# CONTROL.net
KiCad netlist of a schematic drawn in Altium Designer
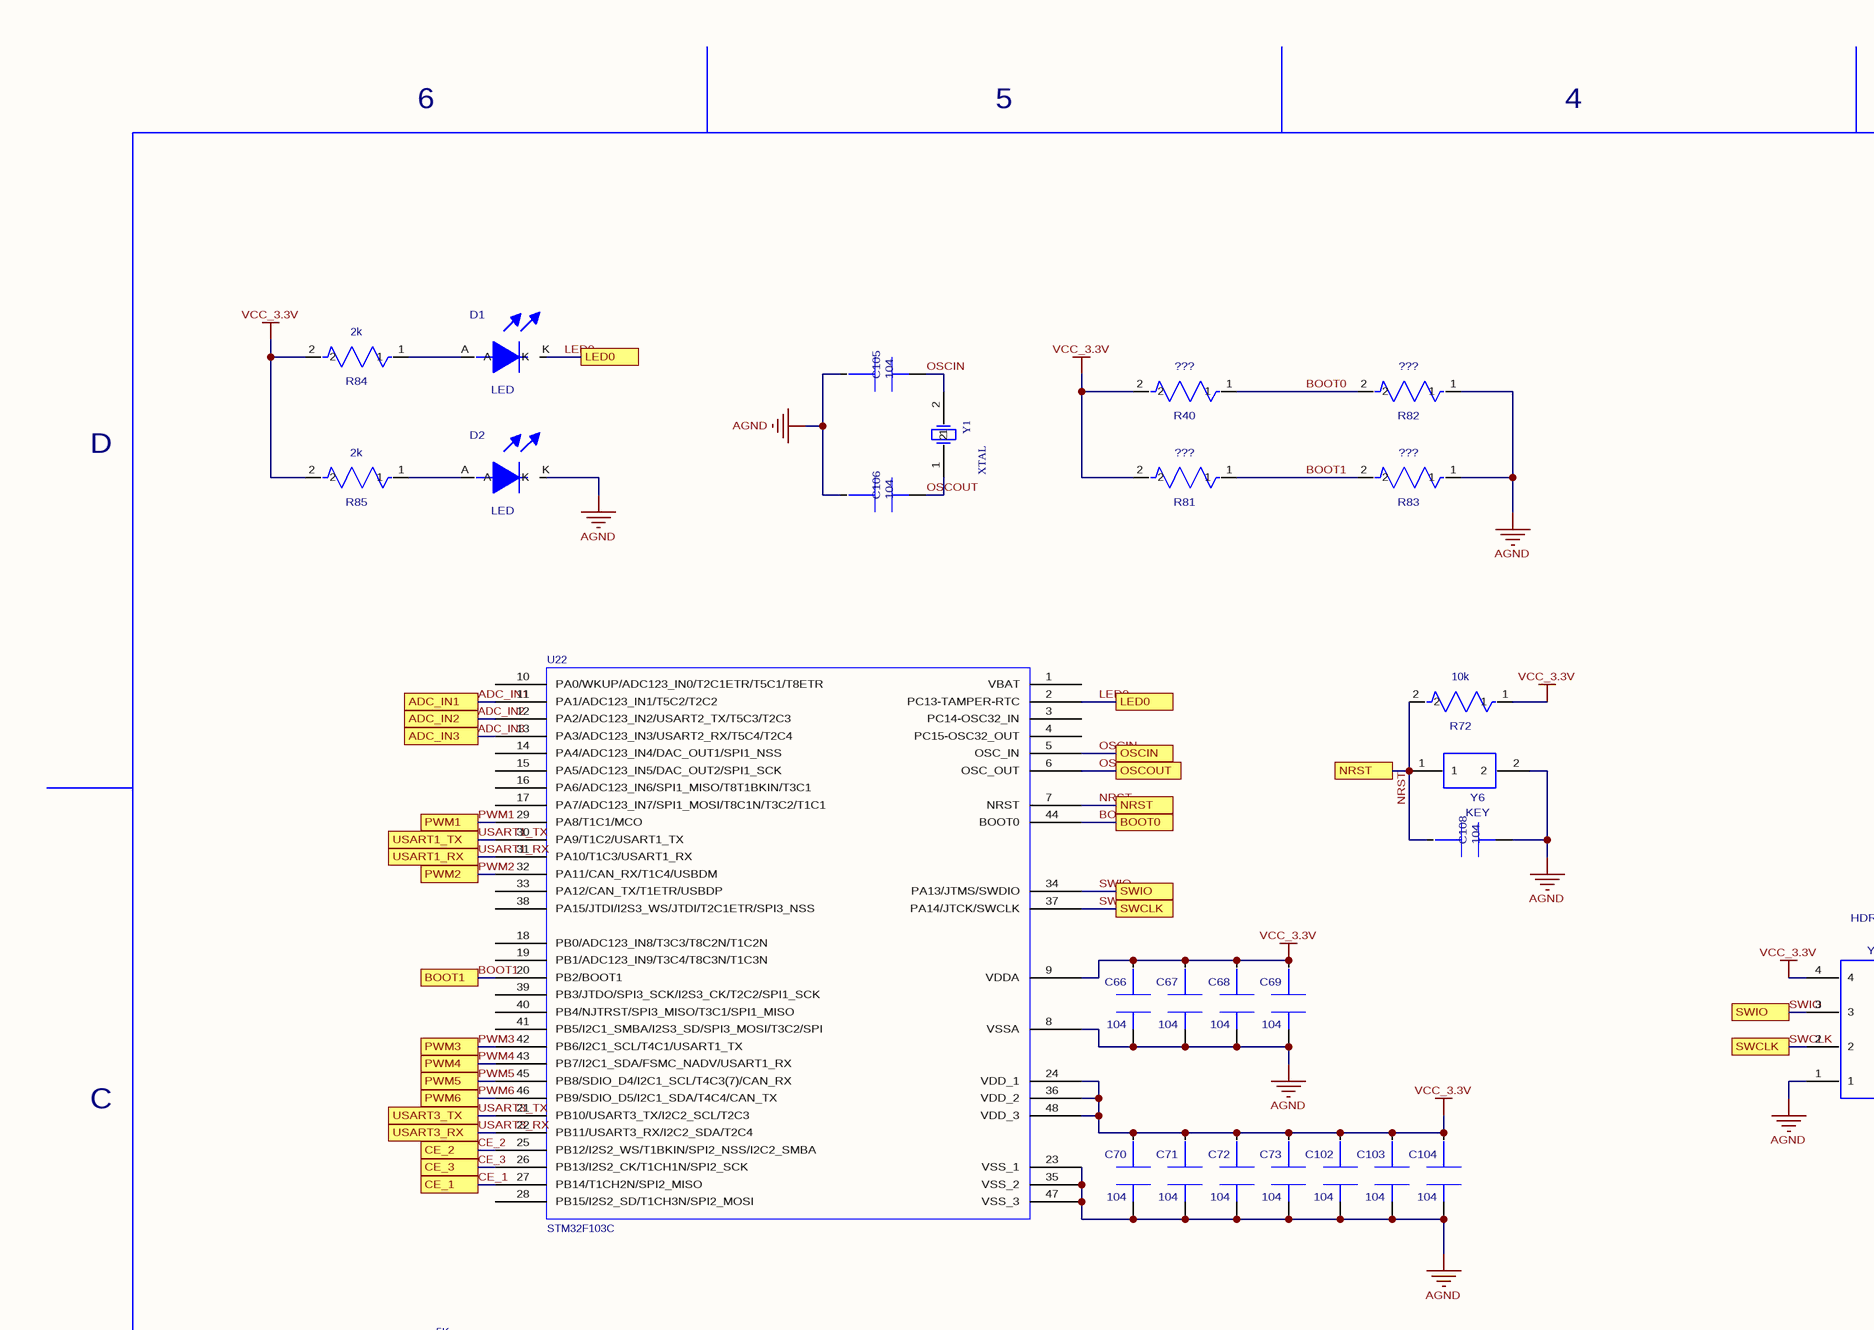
[diagram p0: CONTROL.SchDoc, top left]
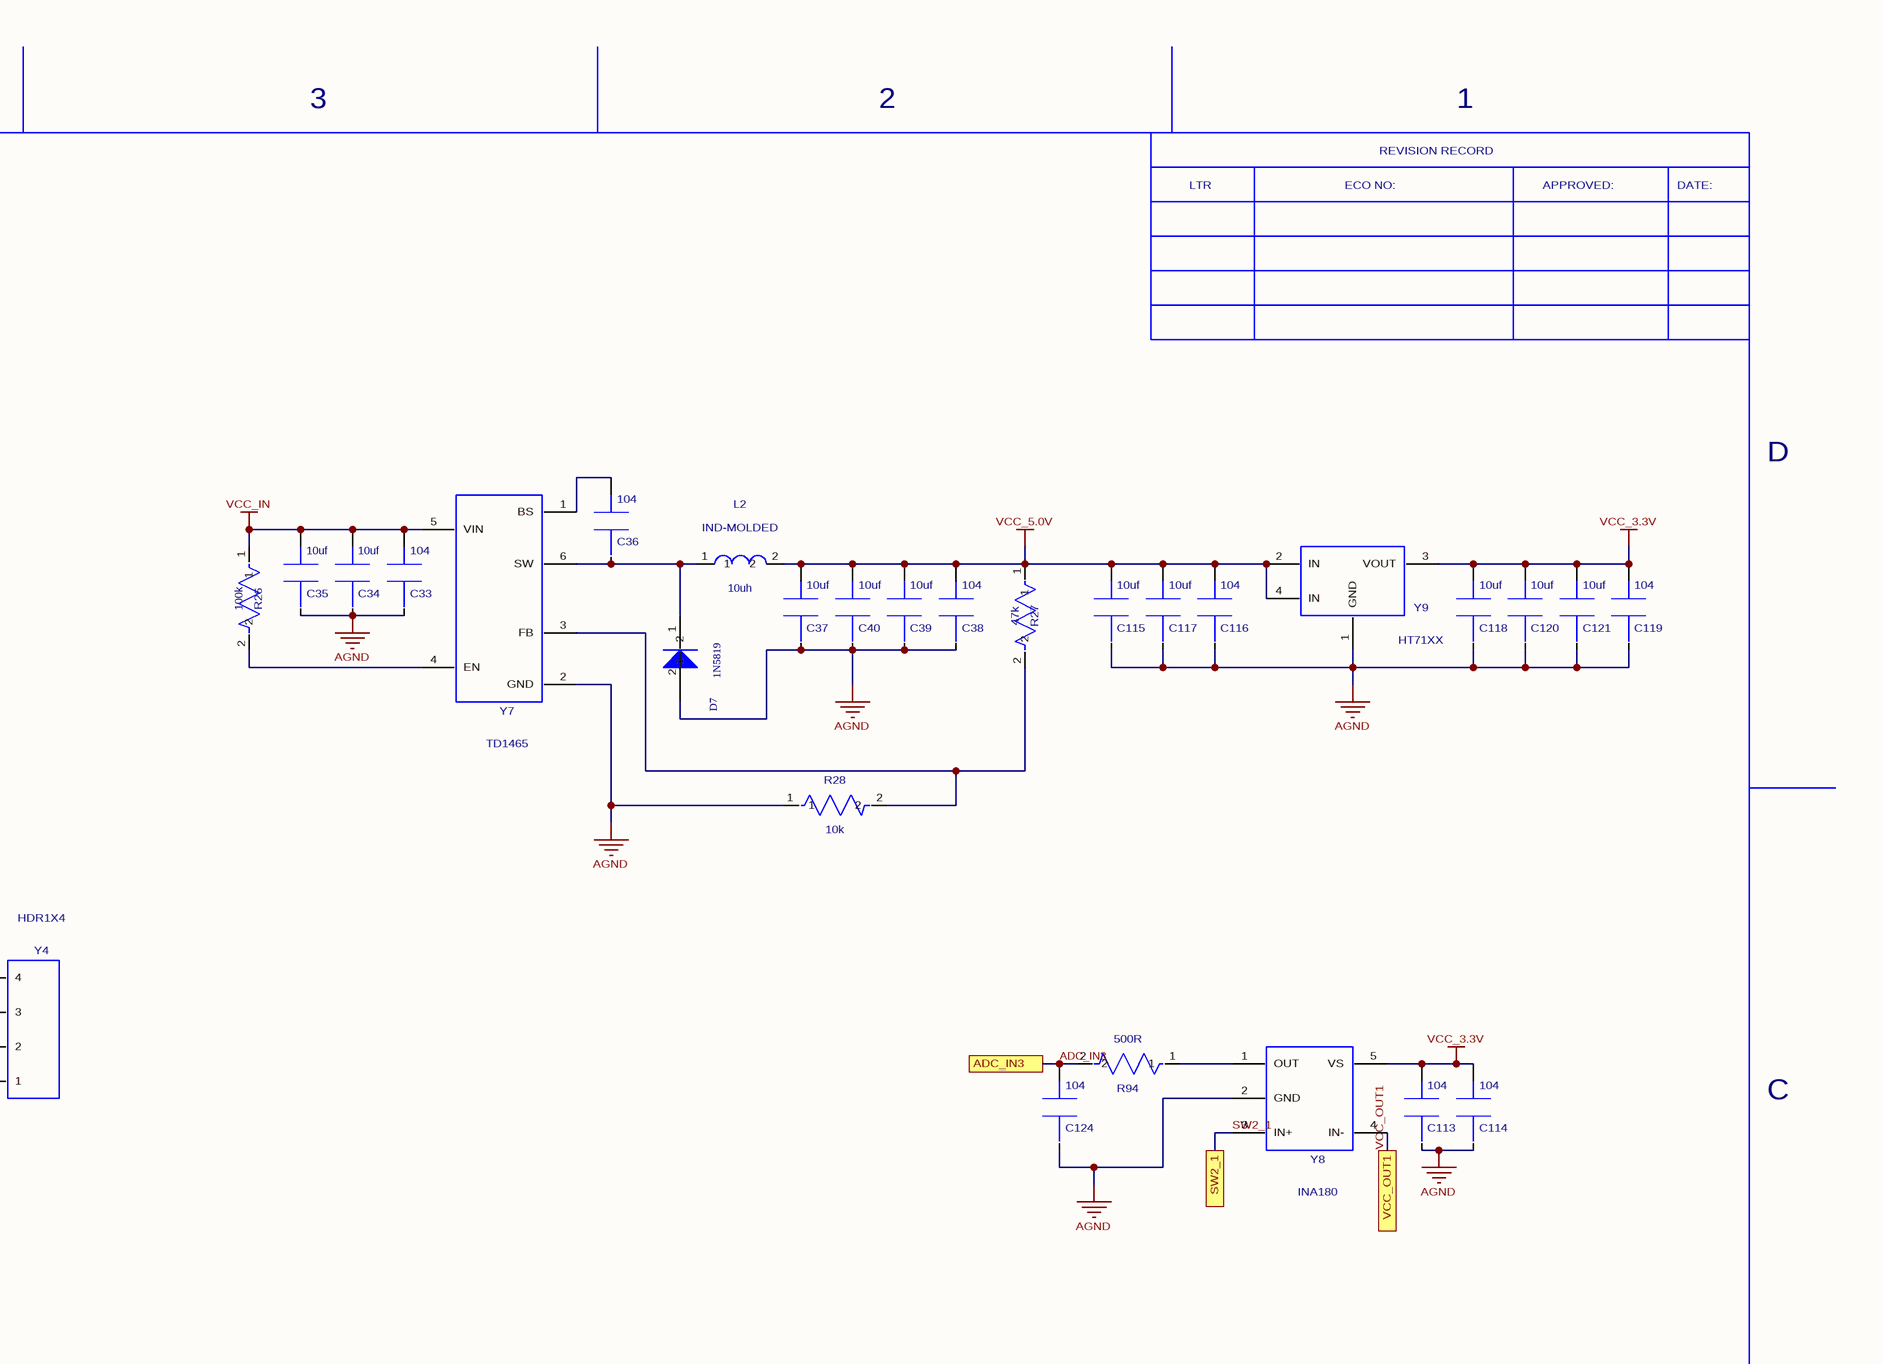
[diagram p1: CONTROL.SchDoc, top right]
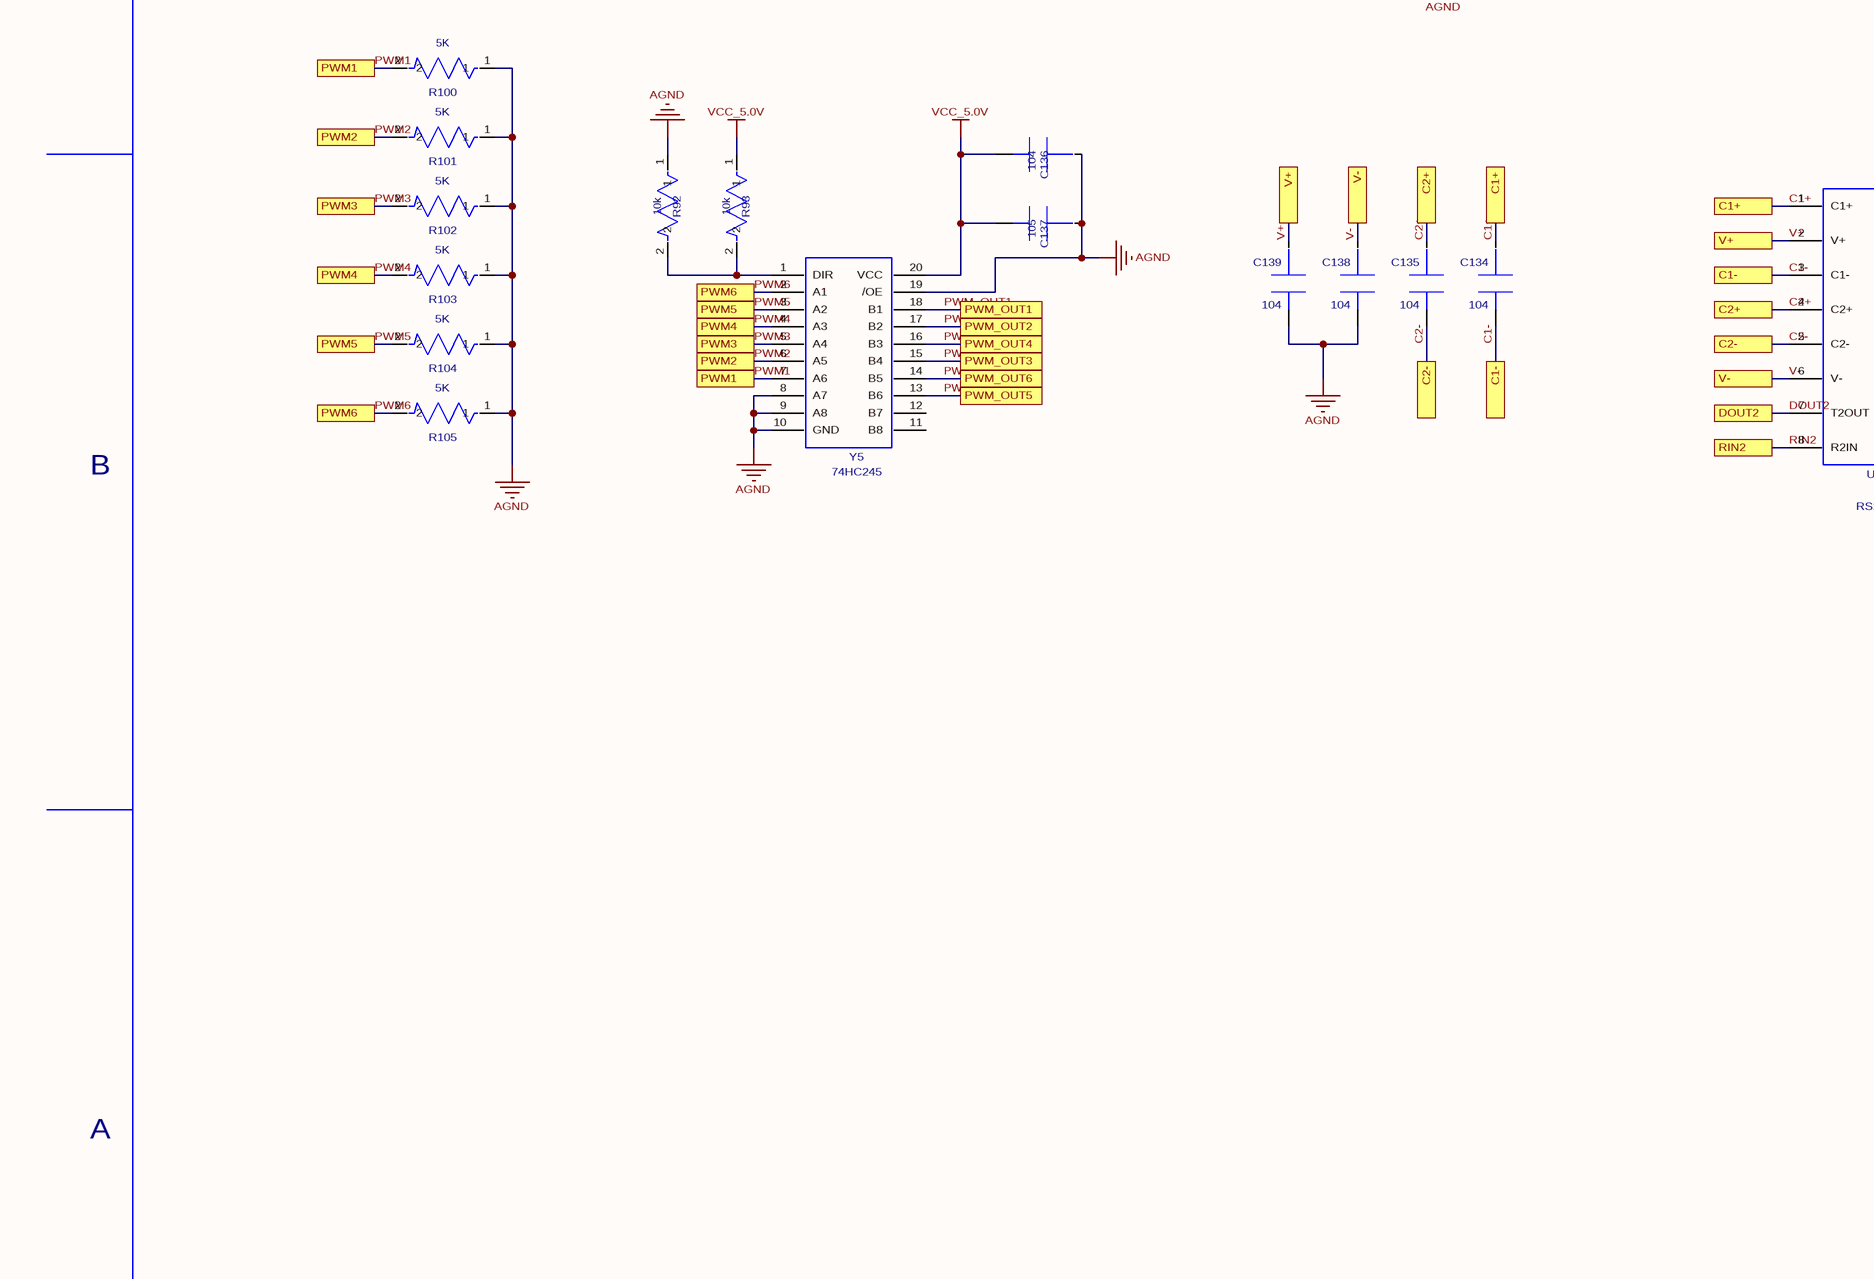
[diagram p2: CONTROL.SchDoc, bottom left]
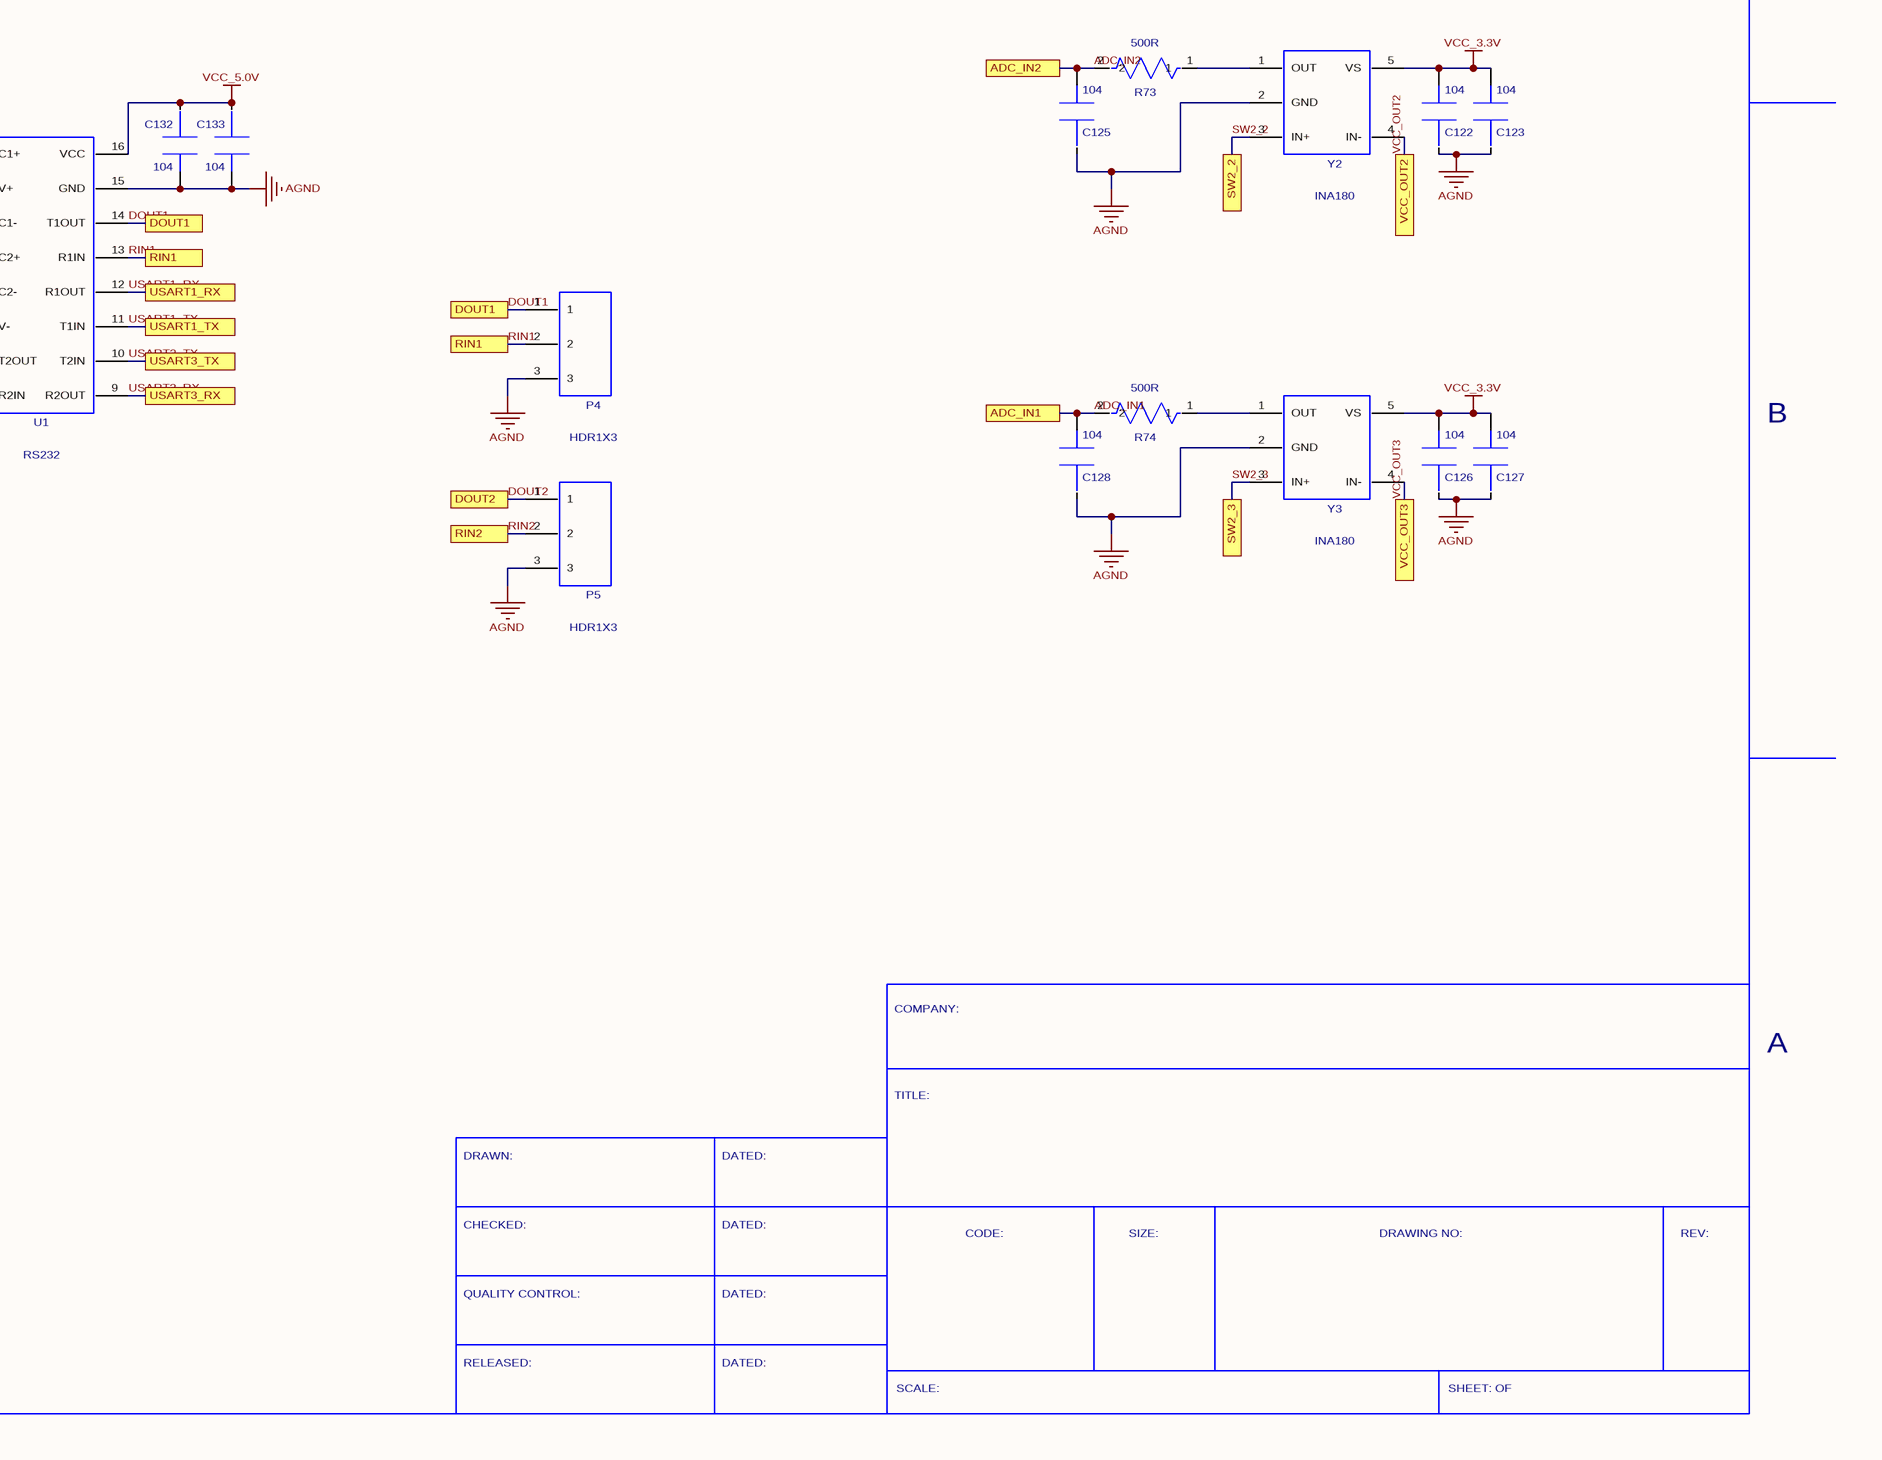
[diagram p3: CONTROL.SchDoc, bottom right]

(export (version "E")
  (design (tool "Eeschema 10.0.6"))
  (components
    (comp (ref "C33")
      (value "104")
      (footprint "0805C")
      (description "RADIAL FILM CAPACITOR, MIL-SPEC SIZE CFR04R SIZE 'C'")
      (fields (field (name "TOLERANCE") "???") (field (name "PART NUMBER") "TBD"))
      (libsource (lib "*") (part "CAP-CFR04R-C"))
    )
    (comp (ref "C34")
      (value "10uf")
      (footprint "0805C")
      (description "RADIAL FILM CAPACITOR, MIL-SPEC SIZE CFR04R SIZE 'C'")
      (fields (field (name "TOLERANCE") "???") (field (name "PART NUMBER") "TBD"))
      (libsource (lib "*") (part "CAP-CFR04R-C"))
    )
    (comp (ref "C35")
      (value "10uf")
      (footprint "0805C")
      (description "RADIAL FILM CAPACITOR, MIL-SPEC SIZE CFR04R SIZE 'C'")
      (fields (field (name "TOLERANCE") "???") (field (name "PART NUMBER") "TBD"))
      (libsource (lib "*") (part "CAP-CFR04R-C"))
    )
    (comp (ref "C36")
      (value "104")
      (footprint "0805C")
      (description "RADIAL FILM CAPACITOR, MIL-SPEC SIZE CFR04R SIZE 'C'")
      (fields (field (name "TOLERANCE") "???") (field (name "PART NUMBER") "TBD"))
      (libsource (lib "*") (part "CAP-CFR04R-C"))
    )
    (comp (ref "C37")
      (value "10uf")
      (footprint "0805C")
      (description "RADIAL FILM CAPACITOR, MIL-SPEC SIZE CFR04R SIZE 'C'")
      (fields (field (name "TOLERANCE") "???") (field (name "PART NUMBER") "TBD"))
      (libsource (lib "*") (part "CAP-CFR04R-C"))
    )
    (comp (ref "C38")
      (value "104")
      (footprint "0805C")
      (description "RADIAL FILM CAPACITOR, MIL-SPEC SIZE CFR04R SIZE 'C'")
      (fields (field (name "TOLERANCE") "???") (field (name "PART NUMBER") "TBD"))
      (libsource (lib "*") (part "CAP-CFR04R-C"))
    )
    (comp (ref "C39")
      (value "10uf")
      (footprint "0805C")
      (description "RADIAL FILM CAPACITOR, MIL-SPEC SIZE CFR04R SIZE 'C'")
      (fields (field (name "TOLERANCE") "???") (field (name "PART NUMBER") "TBD"))
      (libsource (lib "*") (part "CAP-CFR04R-C"))
    )
    (comp (ref "C40")
      (value "10uf")
      (footprint "0805C")
      (description "RADIAL FILM CAPACITOR, MIL-SPEC SIZE CFR04R SIZE 'C'")
      (fields (field (name "TOLERANCE") "???") (field (name "PART NUMBER") "TBD"))
      (libsource (lib "*") (part "CAP-CFR04R-C"))
    )
    (comp (ref "C66")
      (value "104")
      (footprint "0805C")
      (description "RADIAL FILM CAPACITOR, MIL-SPEC SIZE CFR04R SIZE 'C'")
      (fields (field (name "TOLERANCE") "???") (field (name "PART NUMBER") "TBD"))
      (libsource (lib "*") (part "CAP-CFR04R-C"))
    )
    (comp (ref "C67")
      (value "104")
      (footprint "0805C")
      (description "RADIAL FILM CAPACITOR, MIL-SPEC SIZE CFR04R SIZE 'C'")
      (fields (field (name "TOLERANCE") "???") (field (name "PART NUMBER") "TBD"))
      (libsource (lib "*") (part "CAP-CFR04R-C"))
    )
    (comp (ref "C68")
      (value "104")
      (footprint "0805C")
      (description "RADIAL FILM CAPACITOR, MIL-SPEC SIZE CFR04R SIZE 'C'")
      (fields (field (name "TOLERANCE") "???") (field (name "PART NUMBER") "TBD"))
      (libsource (lib "*") (part "CAP-CFR04R-C"))
    )
    (comp (ref "C69")
      (value "104")
      (footprint "0805C")
      (description "RADIAL FILM CAPACITOR, MIL-SPEC SIZE CFR04R SIZE 'C'")
      (fields (field (name "TOLERANCE") "???") (field (name "PART NUMBER") "TBD"))
      (libsource (lib "*") (part "CAP-CFR04R-C"))
    )
    (comp (ref "C70")
      (value "104")
      (footprint "0805C")
      (description "RADIAL FILM CAPACITOR, MIL-SPEC SIZE CFR04R SIZE 'C'")
      (fields (field (name "TOLERANCE") "???") (field (name "PART NUMBER") "TBD"))
      (libsource (lib "*") (part "CAP-CFR04R-C"))
    )
    (comp (ref "C71")
      (value "104")
      (footprint "0805C")
      (description "RADIAL FILM CAPACITOR, MIL-SPEC SIZE CFR04R SIZE 'C'")
      (fields (field (name "TOLERANCE") "???") (field (name "PART NUMBER") "TBD"))
      (libsource (lib "*") (part "CAP-CFR04R-C"))
    )
    (comp (ref "C72")
      (value "104")
      (footprint "0805C")
      (description "RADIAL FILM CAPACITOR, MIL-SPEC SIZE CFR04R SIZE 'C'")
      (fields (field (name "TOLERANCE") "???") (field (name "PART NUMBER") "TBD"))
      (libsource (lib "*") (part "CAP-CFR04R-C"))
    )
    (comp (ref "C73")
      (value "104")
      (footprint "0805C")
      (description "RADIAL FILM CAPACITOR, MIL-SPEC SIZE CFR04R SIZE 'C'")
      (fields (field (name "TOLERANCE") "???") (field (name "PART NUMBER") "TBD"))
      (libsource (lib "*") (part "CAP-CFR04R-C"))
    )
    (comp (ref "C102")
      (value "104")
      (footprint "0805C")
      (description "RADIAL FILM CAPACITOR, MIL-SPEC SIZE CFR04R SIZE 'C'")
      (fields (field (name "TOLERANCE") "???") (field (name "PART NUMBER") "TBD"))
      (libsource (lib "*") (part "CAP-CFR04R-C"))
    )
    (comp (ref "C103")
      (value "104")
      (footprint "0805C")
      (description "RADIAL FILM CAPACITOR, MIL-SPEC SIZE CFR04R SIZE 'C'")
      (fields (field (name "TOLERANCE") "???") (field (name "PART NUMBER") "TBD"))
      (libsource (lib "*") (part "CAP-CFR04R-C"))
    )
    (comp (ref "C104")
      (value "104")
      (footprint "0805C")
      (description "RADIAL FILM CAPACITOR, MIL-SPEC SIZE CFR04R SIZE 'C'")
      (fields (field (name "TOLERANCE") "???") (field (name "PART NUMBER") "TBD"))
      (libsource (lib "*") (part "CAP-CFR04R-C"))
    )
    (comp (ref "C105")
      (value "104")
      (footprint "0805C")
      (description "RADIAL FILM CAPACITOR, MIL-SPEC SIZE CFR04R SIZE 'C'")
      (fields (field (name "TOLERANCE") "???") (field (name "PART NUMBER") "TBD"))
      (libsource (lib "*") (part "CAP-CFR04R-C"))
    )
    (comp (ref "C106")
      (value "104")
      (footprint "0805C")
      (description "RADIAL FILM CAPACITOR, MIL-SPEC SIZE CFR04R SIZE 'C'")
      (fields (field (name "TOLERANCE") "???") (field (name "PART NUMBER") "TBD"))
      (libsource (lib "*") (part "CAP-CFR04R-C"))
    )
    (comp (ref "C108")
      (value "104")
      (footprint "0805C")
      (description "RADIAL FILM CAPACITOR, MIL-SPEC SIZE CFR04R SIZE 'C'")
      (fields (field (name "TOLERANCE") "???") (field (name "PART NUMBER") "TBD"))
      (libsource (lib "*") (part "CAP-CFR04R-C"))
    )
    (comp (ref "C113")
      (value "104")
      (footprint "0805C")
      (description "RADIAL FILM CAPACITOR, MIL-SPEC SIZE CFR04R SIZE 'C'")
      (fields (field (name "TOLERANCE") "???") (field (name "PART NUMBER") "TBD"))
      (libsource (lib "*") (part "CAP-CFR04R-C"))
    )
    (comp (ref "C114")
      (value "104")
      (footprint "0805C")
      (description "RADIAL FILM CAPACITOR, MIL-SPEC SIZE CFR04R SIZE 'C'")
      (fields (field (name "TOLERANCE") "???") (field (name "PART NUMBER") "TBD"))
      (libsource (lib "*") (part "CAP-CFR04R-C"))
    )
    (comp (ref "C115")
      (value "10uf")
      (footprint "0805C")
      (description "RADIAL FILM CAPACITOR, MIL-SPEC SIZE CFR04R SIZE 'C'")
      (fields (field (name "TOLERANCE") "???") (field (name "PART NUMBER") "TBD"))
      (libsource (lib "*") (part "CAP-CFR04R-C"))
    )
    (comp (ref "C116")
      (value "104")
      (footprint "0805C")
      (description "RADIAL FILM CAPACITOR, MIL-SPEC SIZE CFR04R SIZE 'C'")
      (fields (field (name "TOLERANCE") "???") (field (name "PART NUMBER") "TBD"))
      (libsource (lib "*") (part "CAP-CFR04R-C"))
    )
    (comp (ref "C117")
      (value "10uf")
      (footprint "0805C")
      (description "RADIAL FILM CAPACITOR, MIL-SPEC SIZE CFR04R SIZE 'C'")
      (fields (field (name "TOLERANCE") "???") (field (name "PART NUMBER") "TBD"))
      (libsource (lib "*") (part "CAP-CFR04R-C"))
    )
    (comp (ref "C118")
      (value "10uf")
      (footprint "0805C")
      (description "RADIAL FILM CAPACITOR, MIL-SPEC SIZE CFR04R SIZE 'C'")
      (fields (field (name "TOLERANCE") "???") (field (name "PART NUMBER") "TBD"))
      (libsource (lib "*") (part "CAP-CFR04R-C"))
    )
    (comp (ref "C119")
      (value "104")
      (footprint "0805C")
      (description "RADIAL FILM CAPACITOR, MIL-SPEC SIZE CFR04R SIZE 'C'")
      (fields (field (name "TOLERANCE") "???") (field (name "PART NUMBER") "TBD"))
      (libsource (lib "*") (part "CAP-CFR04R-C"))
    )
    (comp (ref "C120")
      (value "10uf")
      (footprint "0805C")
      (description "RADIAL FILM CAPACITOR, MIL-SPEC SIZE CFR04R SIZE 'C'")
      (fields (field (name "TOLERANCE") "???") (field (name "PART NUMBER") "TBD"))
      (libsource (lib "*") (part "CAP-CFR04R-C"))
    )
    (comp (ref "C121")
      (value "10uf")
      (footprint "0805C")
      (description "RADIAL FILM CAPACITOR, MIL-SPEC SIZE CFR04R SIZE 'C'")
      (fields (field (name "TOLERANCE") "???") (field (name "PART NUMBER") "TBD"))
      (libsource (lib "*") (part "CAP-CFR04R-C"))
    )
    (comp (ref "C122")
      (value "104")
      (footprint "0805C")
      (description "RADIAL FILM CAPACITOR, MIL-SPEC SIZE CFR04R SIZE 'C'")
      (fields (field (name "TOLERANCE") "???") (field (name "PART NUMBER") "TBD"))
      (libsource (lib "*") (part "CAP-CFR04R-C"))
    )
    (comp (ref "C123")
      (value "104")
      (footprint "0805C")
      (description "RADIAL FILM CAPACITOR, MIL-SPEC SIZE CFR04R SIZE 'C'")
      (fields (field (name "TOLERANCE") "???") (field (name "PART NUMBER") "TBD"))
      (libsource (lib "*") (part "CAP-CFR04R-C"))
    )
    (comp (ref "C124")
      (value "104")
      (footprint "0805C")
      (description "RADIAL FILM CAPACITOR, MIL-SPEC SIZE CFR04R SIZE 'C'")
      (fields (field (name "TOLERANCE") "???") (field (name "PART NUMBER") "TBD"))
      (libsource (lib "*") (part "CAP-CFR04R-C"))
    )
    (comp (ref "C125")
      (value "104")
      (footprint "0805C")
      (description "RADIAL FILM CAPACITOR, MIL-SPEC SIZE CFR04R SIZE 'C'")
      (fields (field (name "TOLERANCE") "???") (field (name "PART NUMBER") "TBD"))
      (libsource (lib "*") (part "CAP-CFR04R-C"))
    )
    (comp (ref "C126")
      (value "104")
      (footprint "0805C")
      (description "RADIAL FILM CAPACITOR, MIL-SPEC SIZE CFR04R SIZE 'C'")
      (fields (field (name "TOLERANCE") "???") (field (name "PART NUMBER") "TBD"))
      (libsource (lib "*") (part "CAP-CFR04R-C"))
    )
    (comp (ref "C127")
      (value "104")
      (footprint "0805C")
      (description "RADIAL FILM CAPACITOR, MIL-SPEC SIZE CFR04R SIZE 'C'")
      (fields (field (name "TOLERANCE") "???") (field (name "PART NUMBER") "TBD"))
      (libsource (lib "*") (part "CAP-CFR04R-C"))
    )
    (comp (ref "C128")
      (value "104")
      (footprint "0805C")
      (description "RADIAL FILM CAPACITOR, MIL-SPEC SIZE CFR04R SIZE 'C'")
      (fields (field (name "TOLERANCE") "???") (field (name "PART NUMBER") "TBD"))
      (libsource (lib "*") (part "CAP-CFR04R-C"))
    )
    (comp (ref "C132")
      (value "104")
      (footprint "0805C")
      (description "RADIAL FILM CAPACITOR, MIL-SPEC SIZE CFR04R SIZE 'C'")
      (fields (field (name "TOLERANCE") "???") (field (name "PART NUMBER") "TBD"))
      (libsource (lib "*") (part "CAP-CFR04R-C"))
    )
    (comp (ref "C133")
      (value "104")
      (footprint "0805C")
      (description "RADIAL FILM CAPACITOR, MIL-SPEC SIZE CFR04R SIZE 'C'")
      (fields (field (name "TOLERANCE") "???") (field (name "PART NUMBER") "TBD"))
      (libsource (lib "*") (part "CAP-CFR04R-C"))
    )
    (comp (ref "C134")
      (value "104")
      (footprint "0805C")
      (description "RADIAL FILM CAPACITOR, MIL-SPEC SIZE CFR04R SIZE 'C'")
      (fields (field (name "TOLERANCE") "???") (field (name "PART NUMBER") "TBD"))
      (libsource (lib "*") (part "CAP-CFR04R-C"))
    )
    (comp (ref "C135")
      (value "104")
      (footprint "0805C")
      (description "RADIAL FILM CAPACITOR, MIL-SPEC SIZE CFR04R SIZE 'C'")
      (fields (field (name "TOLERANCE") "???") (field (name "PART NUMBER") "TBD"))
      (libsource (lib "*") (part "CAP-CFR04R-C"))
    )
    (comp (ref "C136")
      (value "104")
      (footprint "0805C")
      (description "RADIAL FILM CAPACITOR, MIL-SPEC SIZE CFR04R SIZE 'C'")
      (fields (field (name "TOLERANCE") "???") (field (name "PART NUMBER") "TBD"))
      (libsource (lib "*") (part "CAP-CFR04R-C"))
    )
    (comp (ref "C137")
      (value "105")
      (footprint "0603C")
      (description "RADIAL FILM CAPACITOR, MIL-SPEC SIZE CFR04R SIZE 'C'")
      (fields (field (name "TOLERANCE") "???") (field (name "PART NUMBER") "TBD"))
      (libsource (lib "*") (part "CAP-CFR04R-C"))
    )
    (comp (ref "C138")
      (value "104")
      (footprint "0805C")
      (description "RADIAL FILM CAPACITOR, MIL-SPEC SIZE CFR04R SIZE 'C'")
      (fields (field (name "TOLERANCE") "???") (field (name "PART NUMBER") "TBD"))
      (libsource (lib "*") (part "CAP-CFR04R-C"))
    )
    (comp (ref "C139")
      (value "104")
      (footprint "0805C")
      (description "RADIAL FILM CAPACITOR, MIL-SPEC SIZE CFR04R SIZE 'C'")
      (fields (field (name "TOLERANCE") "???") (field (name "PART NUMBER") "TBD"))
      (libsource (lib "*") (part "CAP-CFR04R-C"))
    )
    (comp (ref "D1")
      (value "LED")
      (footprint "0805D")
      (description "LIGHT EMITTING DIODE")
      (libsource (lib "*") (part "LED"))
    )
    (comp (ref "D2")
      (value "LED")
      (footprint "0805D")
      (description "LIGHT EMITTING DIODE")
      (libsource (lib "*") (part "LED"))
    )
    (comp (ref "D7")
      (value "1N5819")
      (footprint "SOD-123_L2.8-W1.8-LS3.7-RD")
      (description "High Conductance Fast Diode")
      (fields (field (name "PUBLISHER") "Altium Limited"))
      (libsource (lib "*") (part "DIODE_1N4148"))
    )
    (comp (ref "L2")
      (value "IND-MOLDED")
      (footprint "L-SMD-0630")
      (description "MOLDED INDUCTOR, 0.5\" PIN SPACING")
      (fields (field (name "ALTIUM_VALUE") "10uh"))
      (libsource (lib "*") (part "IND-MOLDED"))
    )
    (comp (ref "P4") (value "HDR1X3") (footprint "POST_3") (libsource (lib "*") (part "HDR1X3")))
    (comp (ref "P5") (value "HDR1X3") (footprint "POST_3") (libsource (lib "*") (part "HDR1X3")))
    (comp (ref "R26")
      (value "100k")
      (footprint "0603R")
      (description "WIRE WOUND RESISTOR 3.4 X 7.05 MM")
      (fields (field (name "Comment") "RES-WR1"))
      (libsource (lib "*") (part "RES-WR1"))
    )
    (comp (ref "R27")
      (value "47k")
      (footprint "0603R")
      (description "WIRE WOUND RESISTOR 3.4 X 7.05 MM")
      (fields (field (name "Comment") "RES-WR1"))
      (libsource (lib "*") (part "RES-WR1"))
    )
    (comp (ref "R28")
      (value "10k")
      (footprint "0603R")
      (description "WIRE WOUND RESISTOR 3.4 X 7.05 MM")
      (fields (field (name "Comment") "RES-WR1"))
      (libsource (lib "*") (part "RES-WR1"))
    )
    (comp (ref "R40")
      (value "???")
      (footprint "0603R")
      (description "WIRE WOUND RESISTOR 3.4 X 7.05 MM")
      (fields (field (name "Comment") "RES-WR1"))
      (libsource (lib "*") (part "RES-WR1"))
    )
    (comp (ref "R72")
      (value "10k")
      (footprint "0603R")
      (description "WIRE WOUND RESISTOR 3.4 X 7.05 MM")
      (fields (field (name "Comment") "RES-WR1"))
      (libsource (lib "*") (part "RES-WR1"))
    )
    (comp (ref "R73")
      (value "500R")
      (footprint "0603R")
      (description "WIRE WOUND RESISTOR 3.4 X 7.05 MM")
      (fields (field (name "Comment") "RES-WR1"))
      (libsource (lib "*") (part "RES-WR1"))
    )
    (comp (ref "R74")
      (value "500R")
      (footprint "0603R")
      (description "WIRE WOUND RESISTOR 3.4 X 7.05 MM")
      (fields (field (name "Comment") "RES-WR1"))
      (libsource (lib "*") (part "RES-WR1"))
    )
    (comp (ref "R81")
      (value "???")
      (footprint "0603R")
      (description "WIRE WOUND RESISTOR 3.4 X 7.05 MM")
      (fields (field (name "Comment") "RES-WR1"))
      (libsource (lib "*") (part "RES-WR1"))
    )
    (comp (ref "R82")
      (value "???")
      (footprint "0603R")
      (description "WIRE WOUND RESISTOR 3.4 X 7.05 MM")
      (fields (field (name "Comment") "RES-WR1"))
      (libsource (lib "*") (part "RES-WR1"))
    )
    (comp (ref "R83")
      (value "???")
      (footprint "0603R")
      (description "WIRE WOUND RESISTOR 3.4 X 7.05 MM")
      (fields (field (name "Comment") "RES-WR1"))
      (libsource (lib "*") (part "RES-WR1"))
    )
    (comp (ref "R84")
      (value "2k")
      (footprint "0805R")
      (description "WIRE WOUND RESISTOR 3.4 X 7.05 MM")
      (fields (field (name "Comment") "RES-WR1"))
      (libsource (lib "*") (part "RES-WR1"))
    )
    (comp (ref "R85")
      (value "2k")
      (footprint "0805R")
      (description "WIRE WOUND RESISTOR 3.4 X 7.05 MM")
      (fields (field (name "Comment") "RES-WR1"))
      (libsource (lib "*") (part "RES-WR1"))
    )
    (comp (ref "R92")
      (value "10k")
      (footprint "0603R")
      (description "WIRE WOUND RESISTOR 3.4 X 7.05 MM")
      (fields (field (name "Comment") "RES-WR1"))
      (libsource (lib "*") (part "RES-WR1"))
    )
    (comp (ref "R93")
      (value "10k")
      (footprint "0603R")
      (description "WIRE WOUND RESISTOR 3.4 X 7.05 MM")
      (fields (field (name "Comment") "RES-WR1"))
      (libsource (lib "*") (part "RES-WR1"))
    )
    (comp (ref "R94")
      (value "500R")
      (footprint "0603R")
      (description "WIRE WOUND RESISTOR 3.4 X 7.05 MM")
      (fields (field (name "Comment") "RES-WR1"))
      (libsource (lib "*") (part "RES-WR1"))
    )
    (comp (ref "R100")
      (value "5K")
      (footprint "0603R")
      (description "WIRE WOUND RESISTOR 3.4 X 7.05 MM")
      (fields (field (name "Comment") "RES-WR1"))
      (libsource (lib "*") (part "RES-WR1"))
    )
    (comp (ref "R101")
      (value "5K")
      (footprint "0603R")
      (description "WIRE WOUND RESISTOR 3.4 X 7.05 MM")
      (fields (field (name "Comment") "RES-WR1"))
      (libsource (lib "*") (part "RES-WR1"))
    )
    (comp (ref "R102")
      (value "5K")
      (footprint "0603R")
      (description "WIRE WOUND RESISTOR 3.4 X 7.05 MM")
      (fields (field (name "Comment") "RES-WR1"))
      (libsource (lib "*") (part "RES-WR1"))
    )
    (comp (ref "R103")
      (value "5K")
      (footprint "0603R")
      (description "WIRE WOUND RESISTOR 3.4 X 7.05 MM")
      (fields (field (name "Comment") "RES-WR1"))
      (libsource (lib "*") (part "RES-WR1"))
    )
    (comp (ref "R104")
      (value "5K")
      (footprint "0603R")
      (description "WIRE WOUND RESISTOR 3.4 X 7.05 MM")
      (fields (field (name "Comment") "RES-WR1"))
      (libsource (lib "*") (part "RES-WR1"))
    )
    (comp (ref "R105")
      (value "5K")
      (footprint "0603R")
      (description "WIRE WOUND RESISTOR 3.4 X 7.05 MM")
      (fields (field (name "Comment") "RES-WR1"))
      (libsource (lib "*") (part "RES-WR1"))
    )
    (comp (ref "U1")
      (value "RS232")
      (footprint "SOP-16_L9.9-W3.9-P1.27-LS6.1-BL")
      (libsource (lib "*") (part "RS232"))
    )
    (comp (ref "U22")
      (value "STM32F103C")
      (footprint "LQFP-48_M")
      (description "STM32单片机48引脚")
      (libsource (lib "*") (part "STM32F103C"))
    )
    (comp (ref "Y1")
      (value "XTAL")
      (footprint "HC-49S_L11.4-W4.8")
      (description "Crystal Oscillator")
      (fields (field (name "PUBLISHER") "Altium Limited"))
      (libsource (lib "*") (part "XTAL"))
    )
    (comp (ref "Y2")
      (value "INA180")
      (footprint "SOT-23-5_L3.0-W1.7-P0.95-LS2.8-BL")
      (libsource (lib "*") (part "INA180"))
    )
    (comp (ref "Y3")
      (value "INA180")
      (footprint "SOT-23-5_L3.0-W1.7-P0.95-LS2.8-BL")
      (libsource (lib "*") (part "INA180"))
    )
    (comp (ref "Y4") (value "HDR1X4") (footprint "HDR1X4") (libsource (lib "*") (part "HDR1X4")))
    (comp (ref "Y5")
      (value "74HC245")
      (footprint "TSSOP-20_L6.5-W4.4-P0.65-LS6.4-BL")
      (libsource (lib "*") (part "74HC04"))
    )
    (comp (ref "Y6") (value "KEY") (footprint "KEY_3_6_2.5") (libsource (lib "*") (part "KEY")))
    (comp (ref "Y7") (value "TD1465") (footprint "SOT-23-6") (libsource (lib "*") (part "TD1465")))
    (comp (ref "Y8")
      (value "INA180")
      (footprint "SOT-23-5_L3.0-W1.7-P0.95-LS2.8-BL")
      (libsource (lib "*") (part "INA180"))
    )
    (comp (ref "Y9")
      (value "HT71XX")
      (footprint "SOT-89-3_L4.5-W2.5-P1.50-LS4.2-BR")
      (libsource (lib "*") (part "HT71XX"))
    )
  )
  (nets
    (net (code "1") (name "/ADC_IN1") (class "Default")
      (node (ref "C128") (pin "2") (pinfunction "2_2") (pintype "passive"))
      (node (ref "R74") (pin "2") (pinfunction "2_2") (pintype "passive"))
      (node (ref "U22") (pin "11") (pinfunction "PA1/ADC123_IN1/T5C2/T2C2_11") (pintype "passive"))
    )
    (net (code "2") (name "/ADC_IN2") (class "Default")
      (node (ref "C125") (pin "2") (pinfunction "2_2") (pintype "passive"))
      (node (ref "R73") (pin "2") (pinfunction "2_2") (pintype "passive"))
      (node (ref "U22") (pin "12") (pinfunction "PA2/ADC123_IN2/USART2_TX/T5C3/T2C3_12") (pintype "passive"))
    )
    (net (code "3") (name "/ADC_IN3") (class "Default")
      (node (ref "C124") (pin "2") (pinfunction "2_2") (pintype "passive"))
      (node (ref "R94") (pin "2") (pinfunction "2_2") (pintype "passive"))
      (node (ref "U22") (pin "13") (pinfunction "PA3/ADC123_IN3/USART2_RX/T5C4/T2C4_13") (pintype "passive"))
    )
    (net (code "4") (name "/BOOT0") (class "Default")
      (node (ref "R40") (pin "1") (pinfunction "1_1") (pintype "passive"))
      (node (ref "R82") (pin "2") (pinfunction "2_2") (pintype "passive"))
      (node (ref "U22") (pin "44") (pinfunction "BOOT0_44") (pintype "passive"))
    )
    (net (code "5") (name "/BOOT1") (class "Default")
      (node (ref "R81") (pin "1") (pinfunction "1_1") (pintype "passive"))
      (node (ref "R83") (pin "2") (pinfunction "2_2") (pintype "passive"))
      (node (ref "U22") (pin "20") (pinfunction "PB2/BOOT1_20") (pintype "passive"))
    )
    (net (code "6") (name "/C1+") (class "Default")
      (node (ref "C134") (pin "1") (pinfunction "1_1") (pintype "passive"))
      (node (ref "U1") (pin "1") (pinfunction "C1+_1") (pintype "passive"))
    )
    (net (code "7") (name "/C1-") (class "Default")
      (node (ref "C134") (pin "2") (pinfunction "2_2") (pintype "passive"))
      (node (ref "U1") (pin "3") (pinfunction "C1-_3") (pintype "passive"))
    )
    (net (code "8") (name "/C2+") (class "Default")
      (node (ref "C135") (pin "1") (pinfunction "1_1") (pintype "passive"))
      (node (ref "U1") (pin "4") (pinfunction "C2+_4") (pintype "passive"))
    )
    (net (code "9") (name "/C2-") (class "Default")
      (node (ref "C135") (pin "2") (pinfunction "2_2") (pintype "passive"))
      (node (ref "U1") (pin "5") (pinfunction "C2-_5") (pintype "passive"))
    )
    (net (code "10") (name "/CE_1") (class "Default")
      (node (ref "U22") (pin "27") (pinfunction "PB14/T1CH2N/SPI2_MISO_27") (pintype "passive"))
    )
    (net (code "11") (name "/CE_2") (class "Default")
      (node (ref "U22") (pin "25") (pinfunction "PB12/I2S2_WS/T1BKIN/SPI2_NSS/I2C2_SMBA_25") (pintype "passive"))
    )
    (net (code "12") (name "/CE_3") (class "Default")
      (node (ref "U22") (pin "26") (pinfunction "PB13/I2S2_CK/T1CH1N/SPI2_SCK_26") (pintype "passive"))
    )
    (net (code "13") (name "/DOUT1") (class "Default")
      (node (ref "P4") (pin "1") (pinfunction "1_1") (pintype "passive"))
      (node (ref "U1") (pin "14") (pinfunction "T1OUT_14") (pintype "passive"))
    )
    (net (code "14") (name "/DOUT2") (class "Default")
      (node (ref "P5") (pin "1") (pinfunction "1_1") (pintype "passive"))
      (node (ref "U1") (pin "7") (pinfunction "T2OUT_7") (pintype "passive"))
    )
    (net (code "15") (name "/LED0") (class "Default")
      (node (ref "D1") (pin "K") (pinfunction "K_K") (pintype "passive"))
      (node (ref "U22") (pin "2") (pinfunction "PC13-TAMPER-RTC_2") (pintype "passive"))
    )
    (net (code "16") (name "/NRST") (class "Default")
      (node (ref "C108") (pin "1") (pinfunction "1_1") (pintype "passive"))
      (node (ref "R72") (pin "2") (pinfunction "2_2") (pintype "passive"))
      (node (ref "U22") (pin "7") (pinfunction "NRST_7") (pintype "passive"))
      (node (ref "Y6") (pin "1") (pinfunction "1_1") (pintype "passive"))
    )
    (net (code "17") (name "/OSCIN") (class "Default")
      (node (ref "C105") (pin "2") (pinfunction "2_2") (pintype "passive"))
      (node (ref "U22") (pin "5") (pinfunction "OSC_IN_5") (pintype "passive"))
      (node (ref "Y1") (pin "2") (pinfunction "2_2") (pintype "passive"))
    )
    (net (code "18") (name "/OSCOUT") (class "Default")
      (node (ref "C106") (pin "2") (pinfunction "2_2") (pintype "passive"))
      (node (ref "U22") (pin "6") (pinfunction "OSC_OUT_6") (pintype "passive"))
      (node (ref "Y1") (pin "1") (pinfunction "1_1") (pintype "passive"))
    )
    (net (code "19") (name "/PWM1") (class "Default")
      (node (ref "R100") (pin "2") (pinfunction "2_2") (pintype "passive"))
      (node (ref "U22") (pin "29") (pinfunction "PA8/T1C1/MCO_29") (pintype "passive"))
      (node (ref "Y5") (pin "7") (pinfunction "A6_7") (pintype "passive"))
    )
    (net (code "20") (name "/PWM2") (class "Default")
      (node (ref "R101") (pin "2") (pinfunction "2_2") (pintype "passive"))
      (node (ref "U22") (pin "32") (pinfunction "PA11/CAN_RX/T1C4/USBDM_32") (pintype "passive"))
      (node (ref "Y5") (pin "6") (pinfunction "A5_6") (pintype "passive"))
    )
    (net (code "21") (name "/PWM3") (class "Default")
      (node (ref "R102") (pin "2") (pinfunction "2_2") (pintype "passive"))
      (node (ref "U22") (pin "42") (pinfunction "PB6/I2C1_SCL/T4C1/USART1_TX_42") (pintype "passive"))
      (node (ref "Y5") (pin "5") (pinfunction "A4_5") (pintype "passive"))
    )
    (net (code "22") (name "/PWM4") (class "Default")
      (node (ref "R103") (pin "2") (pinfunction "2_2") (pintype "passive"))
      (node (ref "U22") (pin "43") (pinfunction "PB7/I2C1_SDA/FSMC_NADV/USART1_RX_43") (pintype "passive"))
      (node (ref "Y5") (pin "4") (pinfunction "A3_4") (pintype "passive"))
    )
    (net (code "23") (name "/PWM5") (class "Default")
      (node (ref "R104") (pin "2") (pinfunction "2_2") (pintype "passive"))
      (node (ref "U22") (pin "45") (pinfunction "PB8/SDIO_D4/I2C1_SCL/T4C3(7)/CAN_RX_45") (pintype "passive"))
      (node (ref "Y5") (pin "3") (pinfunction "A2_3") (pintype "passive"))
    )
    (net (code "24") (name "/PWM6") (class "Default")
      (node (ref "R105") (pin "2") (pinfunction "2_2") (pintype "passive"))
      (node (ref "U22") (pin "46") (pinfunction "PB9/SDIO_D5/I2C1_SDA/T4C4/CAN_TX_46") (pintype "passive"))
      (node (ref "Y5") (pin "2") (pinfunction "A1_2") (pintype "passive"))
    )
    (net (code "25") (name "/PWM_OUT1") (class "Default")
      (node (ref "Y5") (pin "18") (pinfunction "B1_18") (pintype "passive"))
    )
    (net (code "26") (name "/PWM_OUT2") (class "Default")
      (node (ref "Y5") (pin "17") (pinfunction "B2_17") (pintype "passive"))
    )
    (net (code "27") (name "/PWM_OUT3") (class "Default")
      (node (ref "Y5") (pin "15") (pinfunction "B4_15") (pintype "passive"))
    )
    (net (code "28") (name "/PWM_OUT4") (class "Default")
      (node (ref "Y5") (pin "16") (pinfunction "B3_16") (pintype "passive"))
    )
    (net (code "29") (name "/PWM_OUT5") (class "Default")
      (node (ref "Y5") (pin "13") (pinfunction "B6_13") (pintype "passive"))
    )
    (net (code "30") (name "/PWM_OUT6") (class "Default")
      (node (ref "Y5") (pin "14") (pinfunction "B5_14") (pintype "passive"))
    )
    (net (code "31") (name "/RIN1") (class "Default")
      (node (ref "P4") (pin "2") (pinfunction "2_2") (pintype "passive"))
      (node (ref "U1") (pin "13") (pinfunction "R1IN_13") (pintype "passive"))
    )
    (net (code "32") (name "/RIN2") (class "Default")
      (node (ref "P5") (pin "2") (pinfunction "2_2") (pintype "passive"))
      (node (ref "U1") (pin "8") (pinfunction "R2IN_8") (pintype "passive"))
    )
    (net (code "33") (name "/SW2_1") (class "Default")
      (node (ref "Y8") (pin "3") (pinfunction "IN+_3") (pintype "passive"))
    )
    (net (code "34") (name "/SW2_2") (class "Default")
      (node (ref "Y2") (pin "3") (pinfunction "IN+_3") (pintype "passive"))
    )
    (net (code "35") (name "/SW2_3") (class "Default")
      (node (ref "Y3") (pin "3") (pinfunction "IN+_3") (pintype "passive"))
    )
    (net (code "36") (name "/SWCLK") (class "Default")
      (node (ref "U22") (pin "37") (pinfunction "PA14/JTCK/SWCLK_37") (pintype "passive"))
      (node (ref "Y4") (pin "2") (pinfunction "2_2") (pintype "passive"))
    )
    (net (code "37") (name "/SWIO") (class "Default")
      (node (ref "U22") (pin "34") (pinfunction "PA13/JTMS/SWDIO_34") (pintype "passive"))
      (node (ref "Y4") (pin "3") (pinfunction "3_3") (pintype "passive"))
    )
    (net (code "38") (name "/USART1_RX") (class "Default")
      (node (ref "U1") (pin "12") (pinfunction "R1OUT_12") (pintype "passive"))
      (node (ref "U22") (pin "31") (pinfunction "PA10/T1C3/USART1_RX_31") (pintype "passive"))
    )
    (net (code "39") (name "/USART1_TX") (class "Default")
      (node (ref "U1") (pin "11") (pinfunction "T1IN_11") (pintype "passive"))
      (node (ref "U22") (pin "30") (pinfunction "PA9/T1C2/USART1_TX_30") (pintype "passive"))
    )
    (net (code "40") (name "/USART3_RX") (class "Default")
      (node (ref "U1") (pin "9") (pinfunction "R2OUT_9") (pintype "passive"))
      (node (ref "U22") (pin "22") (pinfunction "PB11/USART3_RX/I2C2_SDA/T2C4_22") (pintype "passive"))
    )
    (net (code "41") (name "/USART3_TX") (class "Default")
      (node (ref "U1") (pin "10") (pinfunction "T2IN_10") (pintype "passive"))
      (node (ref "U22") (pin "21") (pinfunction "PB10/USART3_TX/I2C2_SCL/T2C3_21") (pintype "passive"))
    )
    (net (code "42") (name "/V+") (class "Default")
      (node (ref "C139") (pin "1") (pinfunction "1_1") (pintype "passive"))
      (node (ref "U1") (pin "2") (pinfunction "V+_2") (pintype "passive"))
    )
    (net (code "43") (name "/V-") (class "Default")
      (node (ref "C138") (pin "1") (pinfunction "1_1") (pintype "passive"))
      (node (ref "U1") (pin "6") (pinfunction "V-_6") (pintype "passive"))
    )
    (net (code "44") (name "/VCC_OUT1") (class "Default")
      (node (ref "Y8") (pin "4") (pinfunction "IN-_4") (pintype "passive"))
    )
    (net (code "45") (name "/VCC_OUT2") (class "Default")
      (node (ref "Y2") (pin "4") (pinfunction "IN-_4") (pintype "passive"))
    )
    (net (code "46") (name "/VCC_OUT3") (class "Default")
      (node (ref "Y3") (pin "4") (pinfunction "IN-_4") (pintype "passive"))
    )
    (net (code "47") (name "AGND") (class "Default")
      (node (ref "C102") (pin "2") (pinfunction "2_2") (pintype "passive"))
      (node (ref "C103") (pin "2") (pinfunction "2_2") (pintype "passive"))
      (node (ref "C104") (pin "2") (pinfunction "2_2") (pintype "passive"))
      (node (ref "C105") (pin "1") (pinfunction "1_1") (pintype "passive"))
      (node (ref "C106") (pin "1") (pinfunction "1_1") (pintype "passive"))
      (node (ref "C108") (pin "2") (pinfunction "2_2") (pintype "passive"))
      (node (ref "C113") (pin "1") (pinfunction "1_1") (pintype "passive"))
      (node (ref "C114") (pin "1") (pinfunction "1_1") (pintype "passive"))
      (node (ref "C115") (pin "1") (pinfunction "1_1") (pintype "passive"))
      (node (ref "C116") (pin "1") (pinfunction "1_1") (pintype "passive"))
      (node (ref "C117") (pin "1") (pinfunction "1_1") (pintype "passive"))
      (node (ref "C118") (pin "1") (pinfunction "1_1") (pintype "passive"))
      (node (ref "C119") (pin "1") (pinfunction "1_1") (pintype "passive"))
      (node (ref "C120") (pin "1") (pinfunction "1_1") (pintype "passive"))
      (node (ref "C121") (pin "1") (pinfunction "1_1") (pintype "passive"))
      (node (ref "C122") (pin "1") (pinfunction "1_1") (pintype "passive"))
      (node (ref "C123") (pin "1") (pinfunction "1_1") (pintype "passive"))
      (node (ref "C124") (pin "1") (pinfunction "1_1") (pintype "passive"))
      (node (ref "C125") (pin "1") (pinfunction "1_1") (pintype "passive"))
      (node (ref "C126") (pin "1") (pinfunction "1_1") (pintype "passive"))
      (node (ref "C127") (pin "1") (pinfunction "1_1") (pintype "passive"))
      (node (ref "C128") (pin "1") (pinfunction "1_1") (pintype "passive"))
      (node (ref "C132") (pin "2") (pinfunction "2_2") (pintype "passive"))
      (node (ref "C133") (pin "2") (pinfunction "2_2") (pintype "passive"))
      (node (ref "C136") (pin "1") (pinfunction "1_1") (pintype "passive"))
      (node (ref "C137") (pin "1") (pinfunction "1_1") (pintype "passive"))
      (node (ref "C138") (pin "2") (pinfunction "2_2") (pintype "passive"))
      (node (ref "C139") (pin "2") (pinfunction "2_2") (pintype "passive"))
      (node (ref "C33") (pin "1") (pinfunction "1_1") (pintype "passive"))
      (node (ref "C34") (pin "1") (pinfunction "1_1") (pintype "passive"))
      (node (ref "C35") (pin "1") (pinfunction "1_1") (pintype "passive"))
      (node (ref "C37") (pin "1") (pinfunction "1_1") (pintype "passive"))
      (node (ref "C38") (pin "1") (pinfunction "1_1") (pintype "passive"))
      (node (ref "C39") (pin "1") (pinfunction "1_1") (pintype "passive"))
      (node (ref "C40") (pin "1") (pinfunction "1_1") (pintype "passive"))
      (node (ref "C66") (pin "2") (pinfunction "2_2") (pintype "passive"))
      (node (ref "C67") (pin "2") (pinfunction "2_2") (pintype "passive"))
      (node (ref "C68") (pin "2") (pinfunction "2_2") (pintype "passive"))
      (node (ref "C69") (pin "2") (pinfunction "2_2") (pintype "passive"))
      (node (ref "C70") (pin "2") (pinfunction "2_2") (pintype "passive"))
      (node (ref "C71") (pin "2") (pinfunction "2_2") (pintype "passive"))
      (node (ref "C72") (pin "2") (pinfunction "2_2") (pintype "passive"))
      (node (ref "C73") (pin "2") (pinfunction "2_2") (pintype "passive"))
      (node (ref "D2") (pin "K") (pinfunction "K_K") (pintype "passive"))
      (node (ref "D7") (pin "2") (pinfunction "2_2") (pintype "passive"))
      (node (ref "P4") (pin "3") (pinfunction "3_3") (pintype "passive"))
      (node (ref "P5") (pin "3") (pinfunction "3_3") (pintype "passive"))
      (node (ref "R100") (pin "1") (pinfunction "1_1") (pintype "passive"))
      (node (ref "R101") (pin "1") (pinfunction "1_1") (pintype "passive"))
      (node (ref "R102") (pin "1") (pinfunction "1_1") (pintype "passive"))
      (node (ref "R103") (pin "1") (pinfunction "1_1") (pintype "passive"))
      (node (ref "R104") (pin "1") (pinfunction "1_1") (pintype "passive"))
      (node (ref "R105") (pin "1") (pinfunction "1_1") (pintype "passive"))
      (node (ref "R28") (pin "1") (pinfunction "1_1") (pintype "passive"))
      (node (ref "R82") (pin "1") (pinfunction "1_1") (pintype "passive"))
      (node (ref "R83") (pin "1") (pinfunction "1_1") (pintype "passive"))
      (node (ref "R92") (pin "1") (pinfunction "1_1") (pintype "passive"))
      (node (ref "U1") (pin "15") (pinfunction "GND_15") (pintype "passive"))
      (node (ref "U22") (pin "23") (pinfunction "VSS_1_23") (pintype "passive"))
      (node (ref "U22") (pin "35") (pinfunction "VSS_2_35") (pintype "passive"))
      (node (ref "U22") (pin "47") (pinfunction "VSS_3_47") (pintype "passive"))
      (node (ref "U22") (pin "8") (pinfunction "VSSA_8") (pintype "passive"))
      (node (ref "Y2") (pin "2") (pinfunction "GND_2") (pintype "passive"))
      (node (ref "Y3") (pin "2") (pinfunction "GND_2") (pintype "passive"))
      (node (ref "Y4") (pin "1") (pinfunction "1_1") (pintype "passive"))
      (node (ref "Y5") (pin "10") (pinfunction "GND_10") (pintype "passive"))
      (node (ref "Y5") (pin "19") (pinfunction "/OE_19") (pintype "passive"))
      (node (ref "Y5") (pin "8") (pinfunction "A7_8") (pintype "passive"))
      (node (ref "Y5") (pin "9") (pinfunction "A8_9") (pintype "passive"))
      (node (ref "Y6") (pin "2") (pinfunction "2_2") (pintype "passive"))
      (node (ref "Y7") (pin "2") (pinfunction "GND_2") (pintype "passive"))
      (node (ref "Y8") (pin "2") (pinfunction "GND_2") (pintype "passive"))
      (node (ref "Y9") (pin "1") (pinfunction "GND_1") (pintype "passive"))
    )
    (net (code "48") (name "Net-(D1-PadA)") (class "Default")
      (node (ref "D1") (pin "A") (pinfunction "A_A") (pintype "passive"))
      (node (ref "R84") (pin "1") (pinfunction "1_1") (pintype "passive"))
    )
    (net (code "49") (name "Net-(D2-PadA)") (class "Default")
      (node (ref "D2") (pin "A") (pinfunction "A_A") (pintype "passive"))
      (node (ref "R85") (pin "1") (pinfunction "1_1") (pintype "passive"))
    )
    (net (code "50") (name "Net-(Y2-OUT)") (class "Default")
      (node (ref "R73") (pin "1") (pinfunction "1_1") (pintype "passive"))
      (node (ref "Y2") (pin "1") (pinfunction "OUT_1") (pintype "passive"))
    )
    (net (code "51") (name "Net-(Y3-OUT)") (class "Default")
      (node (ref "R74") (pin "1") (pinfunction "1_1") (pintype "passive"))
      (node (ref "Y3") (pin "1") (pinfunction "OUT_1") (pintype "passive"))
    )
    (net (code "52") (name "Net-(Y5-DIR)") (class "Default")
      (node (ref "R92") (pin "2") (pinfunction "2_2") (pintype "passive"))
      (node (ref "R93") (pin "2") (pinfunction "2_2") (pintype "passive"))
      (node (ref "Y5") (pin "1") (pinfunction "DIR_1") (pintype "passive"))
    )
    (net (code "53") (name "Net-(Y7-BS)") (class "Default")
      (node (ref "C36") (pin "2") (pinfunction "2_2") (pintype "passive"))
      (node (ref "Y7") (pin "1") (pinfunction "BS_1") (pintype "passive"))
    )
    (net (code "54") (name "Net-(Y7-EN)") (class "Default")
      (node (ref "R26") (pin "2") (pinfunction "2_2") (pintype "passive"))
      (node (ref "Y7") (pin "4") (pinfunction "EN_4") (pintype "passive"))
    )
    (net (code "55") (name "Net-(Y7-FB)") (class "Default")
      (node (ref "R27") (pin "2") (pinfunction "2_2") (pintype "passive"))
      (node (ref "R28") (pin "2") (pinfunction "2_2") (pintype "passive"))
      (node (ref "Y7") (pin "3") (pinfunction "FB_3") (pintype "passive"))
    )
    (net (code "56") (name "Net-(Y7-SW)") (class "Default")
      (node (ref "C36") (pin "1") (pinfunction "1_1") (pintype "passive"))
      (node (ref "D7") (pin "1") (pinfunction "1_1") (pintype "passive"))
      (node (ref "L2") (pin "1") (pinfunction "1_1") (pintype "passive"))
      (node (ref "Y7") (pin "6") (pinfunction "SW_6") (pintype "passive"))
    )
    (net (code "57") (name "Net-(Y8-OUT)") (class "Default")
      (node (ref "R94") (pin "1") (pinfunction "1_1") (pintype "passive"))
      (node (ref "Y8") (pin "1") (pinfunction "OUT_1") (pintype "passive"))
    )
    (net (code "58") (name "VCC_3.3V") (class "Default")
      (node (ref "C102") (pin "1") (pinfunction "1_1") (pintype "passive"))
      (node (ref "C103") (pin "1") (pinfunction "1_1") (pintype "passive"))
      (node (ref "C104") (pin "1") (pinfunction "1_1") (pintype "passive"))
      (node (ref "C113") (pin "2") (pinfunction "2_2") (pintype "passive"))
      (node (ref "C114") (pin "2") (pinfunction "2_2") (pintype "passive"))
      (node (ref "C118") (pin "2") (pinfunction "2_2") (pintype "passive"))
      (node (ref "C119") (pin "2") (pinfunction "2_2") (pintype "passive"))
      (node (ref "C120") (pin "2") (pinfunction "2_2") (pintype "passive"))
      (node (ref "C121") (pin "2") (pinfunction "2_2") (pintype "passive"))
      (node (ref "C122") (pin "2") (pinfunction "2_2") (pintype "passive"))
      (node (ref "C123") (pin "2") (pinfunction "2_2") (pintype "passive"))
      (node (ref "C126") (pin "2") (pinfunction "2_2") (pintype "passive"))
      (node (ref "C127") (pin "2") (pinfunction "2_2") (pintype "passive"))
      (node (ref "C66") (pin "1") (pinfunction "1_1") (pintype "passive"))
      (node (ref "C67") (pin "1") (pinfunction "1_1") (pintype "passive"))
      (node (ref "C68") (pin "1") (pinfunction "1_1") (pintype "passive"))
      (node (ref "C69") (pin "1") (pinfunction "1_1") (pintype "passive"))
      (node (ref "C70") (pin "1") (pinfunction "1_1") (pintype "passive"))
      (node (ref "C71") (pin "1") (pinfunction "1_1") (pintype "passive"))
      (node (ref "C72") (pin "1") (pinfunction "1_1") (pintype "passive"))
      (node (ref "C73") (pin "1") (pinfunction "1_1") (pintype "passive"))
      (node (ref "R40") (pin "2") (pinfunction "2_2") (pintype "passive"))
      (node (ref "R72") (pin "1") (pinfunction "1_1") (pintype "passive"))
      (node (ref "R81") (pin "2") (pinfunction "2_2") (pintype "passive"))
      (node (ref "R84") (pin "2") (pinfunction "2_2") (pintype "passive"))
      (node (ref "R85") (pin "2") (pinfunction "2_2") (pintype "passive"))
      (node (ref "U22") (pin "24") (pinfunction "VDD_1_24") (pintype "passive"))
      (node (ref "U22") (pin "36") (pinfunction "VDD_2_36") (pintype "passive"))
      (node (ref "U22") (pin "48") (pinfunction "VDD_3_48") (pintype "passive"))
      (node (ref "U22") (pin "9") (pinfunction "VDDA_9") (pintype "passive"))
      (node (ref "Y2") (pin "5") (pinfunction "VS_5") (pintype "passive"))
      (node (ref "Y3") (pin "5") (pinfunction "VS_5") (pintype "passive"))
      (node (ref "Y4") (pin "4") (pinfunction "4_4") (pintype "passive"))
      (node (ref "Y8") (pin "5") (pinfunction "VS_5") (pintype "passive"))
      (node (ref "Y9") (pin "3") (pinfunction "VOUT_3") (pintype "passive"))
    )
    (net (code "59") (name "VCC_5.0V") (class "Default")
      (node (ref "C115") (pin "2") (pinfunction "2_2") (pintype "passive"))
      (node (ref "C116") (pin "2") (pinfunction "2_2") (pintype "passive"))
      (node (ref "C117") (pin "2") (pinfunction "2_2") (pintype "passive"))
      (node (ref "C132") (pin "1") (pinfunction "1_1") (pintype "passive"))
      (node (ref "C133") (pin "1") (pinfunction "1_1") (pintype "passive"))
      (node (ref "C136") (pin "2") (pinfunction "2_2") (pintype "passive"))
      (node (ref "C137") (pin "2") (pinfunction "2_2") (pintype "passive"))
      (node (ref "C37") (pin "2") (pinfunction "2_2") (pintype "passive"))
      (node (ref "C38") (pin "2") (pinfunction "2_2") (pintype "passive"))
      (node (ref "C39") (pin "2") (pinfunction "2_2") (pintype "passive"))
      (node (ref "C40") (pin "2") (pinfunction "2_2") (pintype "passive"))
      (node (ref "L2") (pin "2") (pinfunction "2_2") (pintype "passive"))
      (node (ref "R27") (pin "1") (pinfunction "1_1") (pintype "passive"))
      (node (ref "R93") (pin "1") (pinfunction "1_1") (pintype "passive"))
      (node (ref "U1") (pin "16") (pinfunction "VCC_16") (pintype "passive"))
      (node (ref "Y5") (pin "20") (pinfunction "VCC_20") (pintype "passive"))
      (node (ref "Y9") (pin "2") (pinfunction "IN_2") (pintype "passive"))
      (node (ref "Y9") (pin "4") (pinfunction "IN_4") (pintype "passive"))
    )
    (net (code "60") (name "VCC_IN") (class "Default")
      (node (ref "C33") (pin "2") (pinfunction "2_2") (pintype "passive"))
      (node (ref "C34") (pin "2") (pinfunction "2_2") (pintype "passive"))
      (node (ref "C35") (pin "2") (pinfunction "2_2") (pintype "passive"))
      (node (ref "R26") (pin "1") (pinfunction "1_1") (pintype "passive"))
      (node (ref "Y7") (pin "5") (pinfunction "VIN_5") (pintype "passive"))
    )
    (net (code "61") (name "unconnected-(U22-PA0{slash}WKUP{slash}ADC123_IN0{slash}T2C1ETR{slash}T5C1{slash}T8ETR-Pad10)") (class "Default")
      (node (ref "U22") (pin "10") (pinfunction "PA0/WKUP/ADC123_IN0/T2C1ETR/T5C1/T8ETR_10") (pintype "passive"))
    )
    (net (code "62") (name "unconnected-(U22-PA4{slash}ADC123_IN4{slash}DAC_OUT1{slash}SPI1_NSS-Pad14)") (class "Default")
      (node (ref "U22") (pin "14") (pinfunction "PA4/ADC123_IN4/DAC_OUT1/SPI1_NSS_14") (pintype "passive"))
    )
    (net (code "63") (name "unconnected-(U22-PA5{slash}ADC123_IN5{slash}DAC_OUT2{slash}SPI1_SCK-Pad15)") (class "Default")
      (node (ref "U22") (pin "15") (pinfunction "PA5/ADC123_IN5/DAC_OUT2/SPI1_SCK_15") (pintype "passive"))
    )
    (net (code "64") (name "unconnected-(U22-PA6{slash}ADC123_IN6{slash}SPI1_MISO{slash}T8T1BKIN{slash}T3C1-Pad16)") (class "Default")
      (node (ref "U22") (pin "16") (pinfunction "PA6/ADC123_IN6/SPI1_MISO/T8T1BKIN/T3C1_16") (pintype "passive"))
    )
    (net (code "65") (name "unconnected-(U22-PA7{slash}ADC123_IN7{slash}SPI1_MOSI{slash}T8C1N{slash}T3C2{slash}T1C1-Pad17)") (class "Default")
      (node (ref "U22") (pin "17") (pinfunction "PA7/ADC123_IN7/SPI1_MOSI/T8C1N/T3C2/T1C1_17") (pintype "passive"))
    )
    (net (code "66") (name "unconnected-(U22-PA12{slash}CAN_TX{slash}T1ETR{slash}USBDP-Pad33)") (class "Default")
      (node (ref "U22") (pin "33") (pinfunction "PA12/CAN_TX/T1ETR/USBDP_33") (pintype "passive"))
    )
    (net (code "67") (name "unconnected-(U22-PA15{slash}JTDI{slash}I2S3_WS{slash}JTDI{slash}T2C1ETR{slash}SPI3_NSS-Pad38)") (class "Default")
      (node (ref "U22") (pin "38") (pinfunction "PA15/JTDI/I2S3_WS/JTDI/T2C1ETR/SPI3_NSS_38") (pintype "passive"))
    )
    (net (code "68") (name "unconnected-(U22-PB0{slash}ADC123_IN8{slash}T3C3{slash}T8C2N{slash}T1C2N-Pad18)") (class "Default")
      (node (ref "U22") (pin "18") (pinfunction "PB0/ADC123_IN8/T3C3/T8C2N/T1C2N_18") (pintype "passive"))
    )
    (net (code "69") (name "unconnected-(U22-PB1{slash}ADC123_IN9{slash}T3C4{slash}T8C3N{slash}T1C3N-Pad19)") (class "Default")
      (node (ref "U22") (pin "19") (pinfunction "PB1/ADC123_IN9/T3C4/T8C3N/T1C3N_19") (pintype "passive"))
    )
    (net (code "70") (name "unconnected-(U22-PB3{slash}JTDO{slash}SPI3_SCK{slash}I2S3_CK{slash}T2C2{slash}SPI1_SCK-Pad39)") (class "Default")
      (node (ref "U22") (pin "39") (pinfunction "PB3/JTDO/SPI3_SCK/I2S3_CK/T2C2/SPI1_SCK_39") (pintype "passive"))
    )
    (net (code "71") (name "unconnected-(U22-PB4{slash}NJTRST{slash}SPI3_MISO{slash}T3C1{slash}SPI1_MISO-Pad40)") (class "Default")
      (node (ref "U22") (pin "40") (pinfunction "PB4/NJTRST/SPI3_MISO/T3C1/SPI1_MISO_40") (pintype "passive"))
    )
    (net (code "72") (name "unconnected-(U22-PB5{slash}I2C1_SMBA{slash}I2S3_SD{slash}SPI3_MOSI{slash}T3C2{slash}SPI-Pad41)") (class "Default")
      (node (ref "U22") (pin "41") (pinfunction "PB5/I2C1_SMBA/I2S3_SD/SPI3_MOSI/T3C2/SPI_41") (pintype "passive"))
    )
    (net (code "73") (name "unconnected-(U22-PB15{slash}I2S2_SD{slash}T1CH3N{slash}SPI2_MOSI-Pad28)") (class "Default")
      (node (ref "U22") (pin "28") (pinfunction "PB15/I2S2_SD/T1CH3N/SPI2_MOSI_28") (pintype "passive"))
    )
    (net (code "74") (name "unconnected-(U22-PC14-OSC32_IN-Pad3)") (class "Default")
      (node (ref "U22") (pin "3") (pinfunction "PC14-OSC32_IN_3") (pintype "passive"))
    )
    (net (code "75") (name "unconnected-(U22-PC15-OSC32_OUT-Pad4)") (class "Default")
      (node (ref "U22") (pin "4") (pinfunction "PC15-OSC32_OUT_4") (pintype "passive"))
    )
    (net (code "76") (name "unconnected-(U22-VBAT-Pad1)") (class "Default")
      (node (ref "U22") (pin "1") (pinfunction "VBAT_1") (pintype "passive"))
    )
    (net (code "77") (name "unconnected-(Y5-B7-Pad12)") (class "Default")
      (node (ref "Y5") (pin "12") (pinfunction "B7_12") (pintype "passive"))
    )
    (net (code "78") (name "unconnected-(Y5-B8-Pad11)") (class "Default")
      (node (ref "Y5") (pin "11") (pinfunction "B8_11") (pintype "passive"))
    )
  )
)
